# USB2_host_otg.net
KiCad netlist of a schematic drawn in Altium Designer
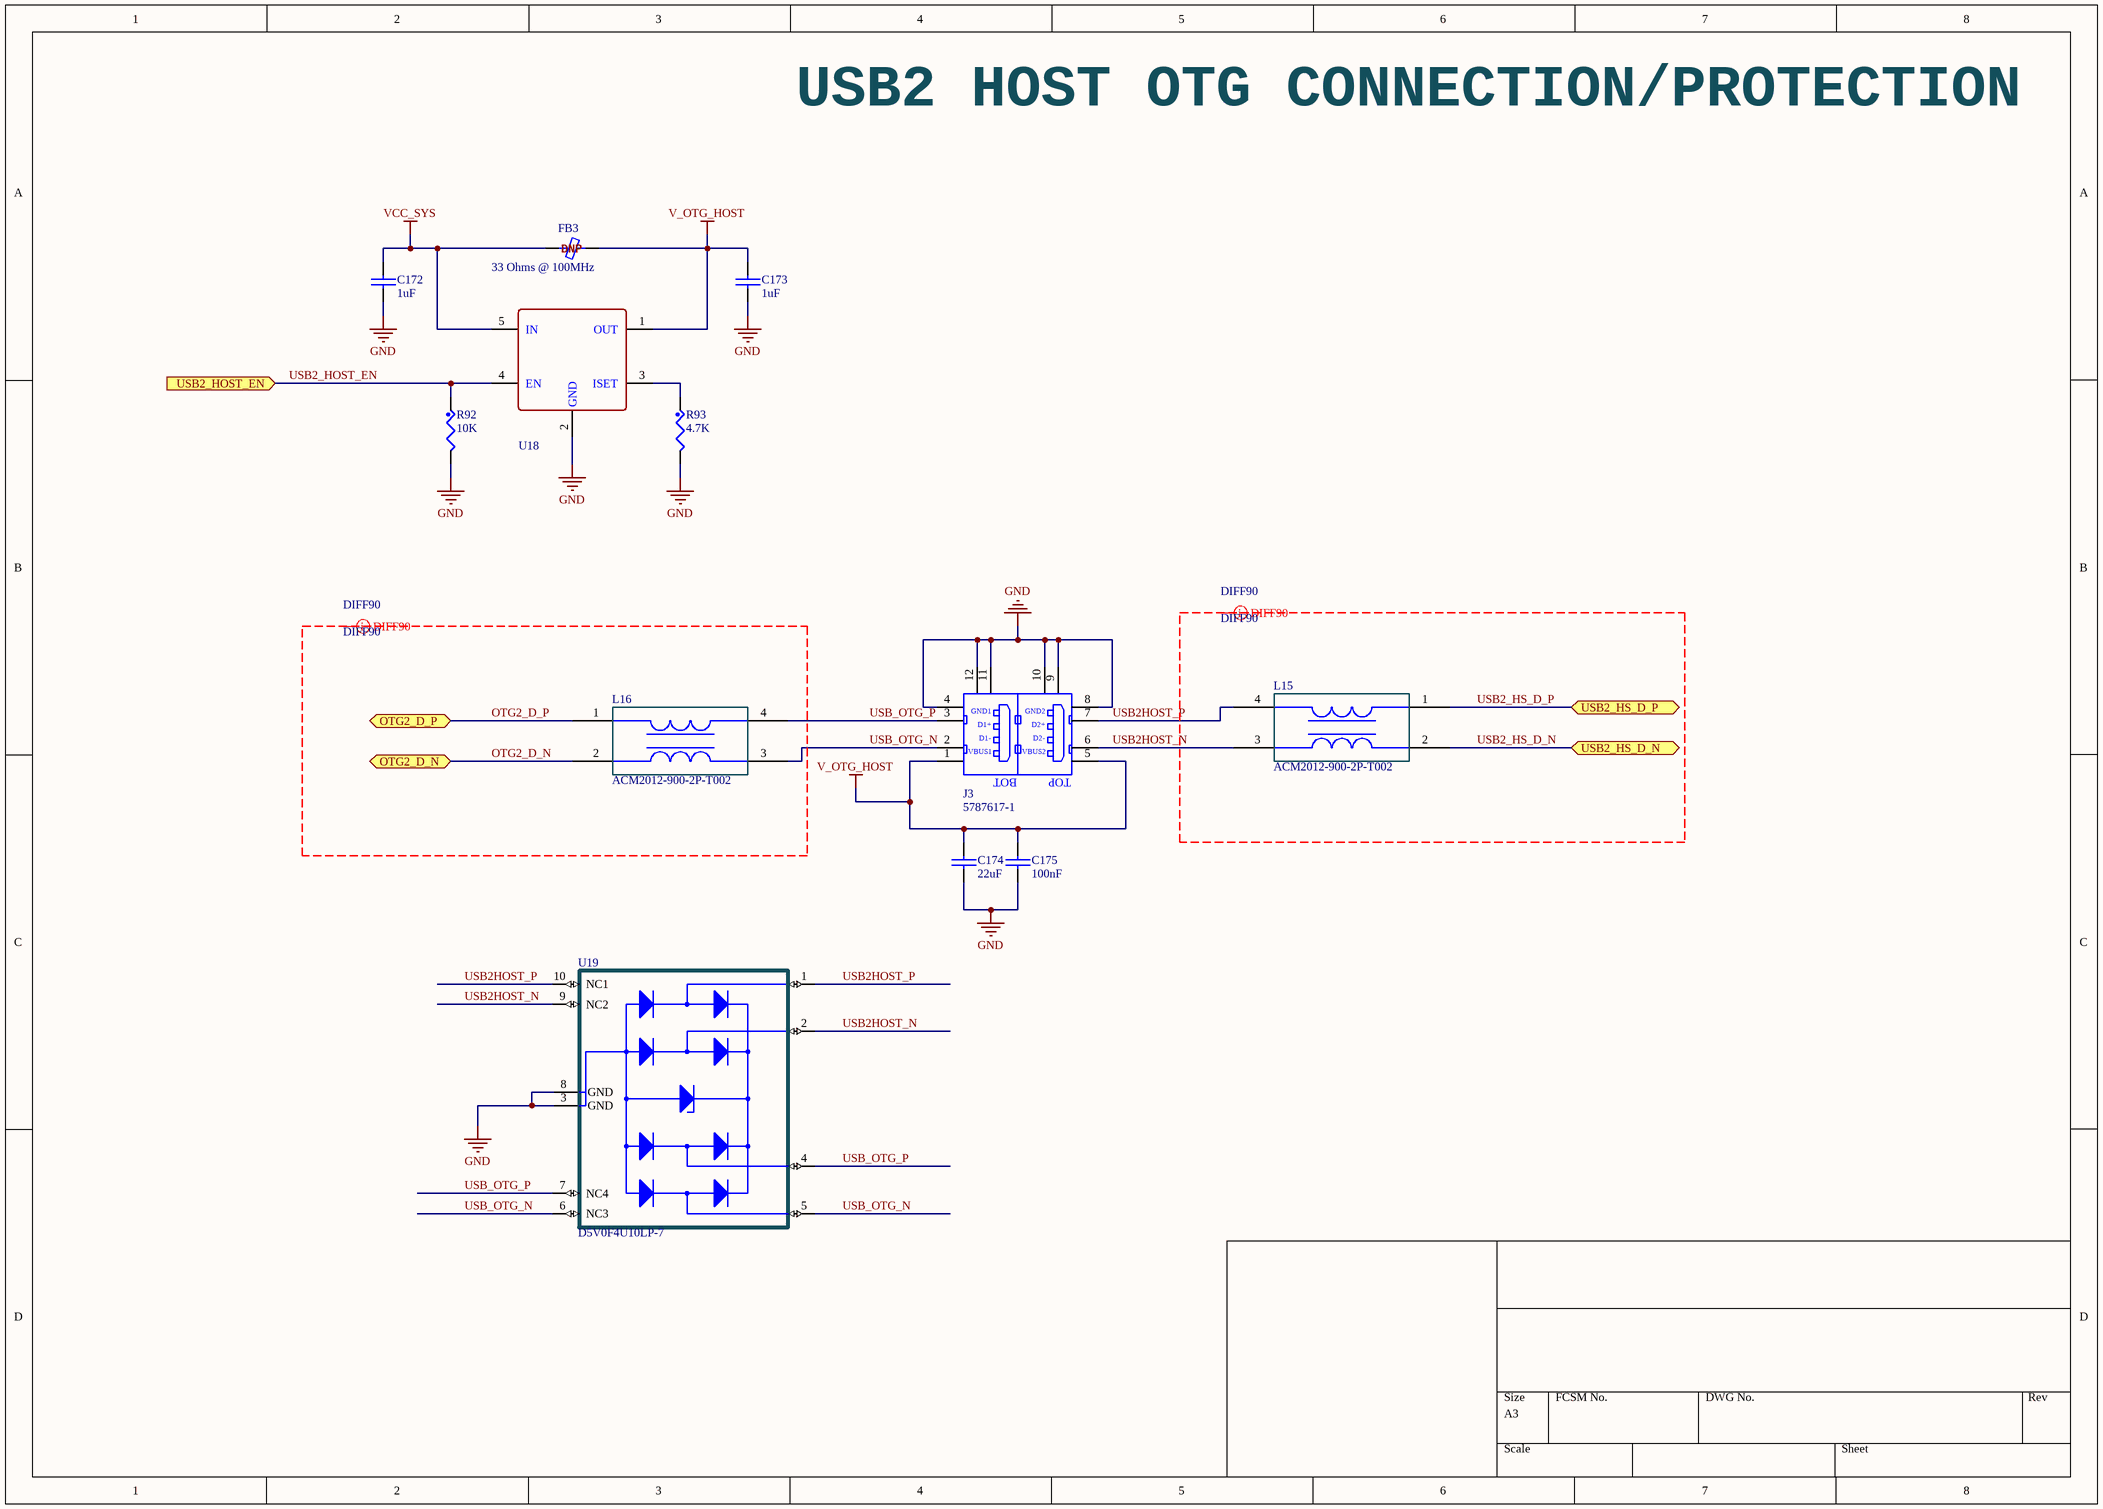
[diagram p0: USB2_host_otg.SchDoc]

(export (version "E")
  (design (tool "Eeschema 10.0.6"))
  (components
    (comp (ref "C172")
      (value "1uF")
      (footprint "0603_CC")
      (libsource (lib "AAR_RockChip_RK3328") (part "CAP_NP"))
    )
    (comp (ref "C173")
      (value "1uF")
      (footprint "0603_CC")
      (libsource (lib "AAR_RockChip_RK3328") (part "CAP_NP"))
    )
    (comp (ref "C174")
      (value "22uF")
      (footprint "0603_CC")
      (libsource (lib "AAR_RockChip_RK3328") (part "CAP_NP"))
    )
    (comp (ref "C175")
      (value "100nF")
      (footprint "0402_CC - C")
      (libsource (lib "AAR_RockChip_RK3328") (part "CAP_NP"))
    )
    (comp (ref "FB3")
      (value "33 Ohms @ 100MHz")
      (footprint "FER 0805_2012")
      (description "FERRITE BEAD 33 OHM 0805 1LN")
      (fields (field (name "PART NUMBER") "Z0805C330ASMST") (field (name "MANUFACTURER") "KEMET"))
      (libsource (lib "Celestial Altium Library - altium_library") (part "Ferrite Chip"))
    )
    (comp (ref "J3")
      (value "5787617-1")
      (footprint "USB-2A")
      (description "CONN RCPT R/A 4OVER4POS GOLD PCB")
      (fields (field (name "MANUFACTURER") "TE Connectivity"))
      (libsource (lib "AAR_RockChip_RK3328") (part "5787617-1_v1.1"))
    )
    (comp (ref "L15")
      (value "ACM2012-900-2P-T002")
      (footprint "FP-ACM2012-MFG")
      (description "CMC 400MA 2LN 90 OHM SMD")
      (fields (field (name "COPYRIGHT") "Copyright (C) 2022 Ultra Librarian. All rights reserved."))
      (libsource (lib "") (part "ACM2012-900-2P-T002_1"))
    )
    (comp (ref "L16")
      (value "ACM2012-900-2P-T002")
      (footprint "FP-ACM2012-MFG")
      (description "CMC 400MA 2LN 90 OHM SMD")
      (fields (field (name "COPYRIGHT") "Copyright (C) 2022 Ultra Librarian. All rights reserved."))
      (libsource (lib "AAR_RockChip_RK3328") (part "ACM2012-900-2P-T002"))
    )
    (comp (ref "R92")
      (value "10K")
      (footprint "0402_CR")
      (libsource (lib "AAR_RockChip_RK3328") (part "RES"))
    )
    (comp (ref "R93")
      (value "4.7K")
      (footprint "0402_CR")
      (libsource (lib "AAR_RockChip_RK3328") (part "RES"))
    )
    (comp (ref "U18")
      (value "Switch")
      (footprint "SOT23_5")
      (fields (field (name "MFR_PART_NO") "SY6280AAC") (field (name "MANUFACTURER") "Silergy"))
      (libsource (lib "AAR_RockChip_RK3328") (part "SY6280A"))
    )
    (comp (ref "U19")
      (value "D5V0F4U10LP-7")
      (footprint "TI_TPD4E05U06DQAR")
      (description "TVS DIODE 5.5VWM 12VC U-DFN2510")
      (fields (field (name "MFR") "Diodes Incorporated") (field (name "CREATOR") "AAR"))
      (libsource (lib "AAR_RockChip_RK3328") (part "D5V0F4U10LP-7"))
    )
  )
  (nets
    (net (code "1") (name "/OTG2_D_N") (class "Default")
      (node (ref "L16") (pin "2") (pinfunction "2_2") (pintype "passive"))
    )
    (net (code "2") (name "/OTG2_D_P") (class "Default")
      (node (ref "L16") (pin "1") (pinfunction "1_1") (pintype "passive"))
    )
    (net (code "3") (name "/USB2HOST_N") (class "Default")
      (node (ref "J3") (pin "6") (pinfunction "D2-_6") (pintype "passive"))
      (node (ref "L15") (pin "3") (pinfunction "3_3") (pintype "passive"))
      (node (ref "U19") (pin "2") (pinfunction "D1-_2") (pintype "bidirectional"))
      (node (ref "U19") (pin "9") (pinfunction "NC2_9") (pintype "bidirectional"))
    )
    (net (code "4") (name "/USB2HOST_P") (class "Default")
      (node (ref "J3") (pin "7") (pinfunction "D2+_7") (pintype "passive"))
      (node (ref "L15") (pin "4") (pinfunction "4_4") (pintype "passive"))
      (node (ref "U19") (pin "1") (pinfunction "D1+_1") (pintype "bidirectional"))
      (node (ref "U19") (pin "10") (pinfunction "NC1_10") (pintype "bidirectional"))
    )
    (net (code "5") (name "/USB2_HOST_EN") (class "Default")
      (node (ref "R92") (pin "1") (pinfunction "1_1") (pintype "passive"))
      (node (ref "U18") (pin "4") (pinfunction "EN_4") (pintype "open_collector"))
    )
    (net (code "6") (name "/USB2_HS_D_N") (class "Default")
      (node (ref "L15") (pin "2") (pinfunction "2_2") (pintype "passive"))
    )
    (net (code "7") (name "/USB2_HS_D_P") (class "Default")
      (node (ref "L15") (pin "1") (pinfunction "1_1") (pintype "passive"))
    )
    (net (code "8") (name "/USB_OTG_N") (class "Default")
      (node (ref "J3") (pin "2") (pinfunction "D-_2") (pintype "passive"))
      (node (ref "L16") (pin "3") (pinfunction "3_3") (pintype "passive"))
      (node (ref "U19") (pin "5") (pinfunction "D2-_5") (pintype "bidirectional"))
      (node (ref "U19") (pin "6") (pinfunction "NC3_6") (pintype "bidirectional"))
    )
    (net (code "9") (name "/USB_OTG_P") (class "Default")
      (node (ref "J3") (pin "3") (pinfunction "D+_3") (pintype "passive"))
      (node (ref "L16") (pin "4") (pinfunction "4_4") (pintype "passive"))
      (node (ref "U19") (pin "4") (pinfunction "D2+_4") (pintype "bidirectional"))
      (node (ref "U19") (pin "7") (pinfunction "NC4_7") (pintype "bidirectional"))
    )
    (net (code "10") (name "GND") (class "Default")
      (node (ref "C172") (pin "2") (pinfunction "2_2") (pintype "passive"))
      (node (ref "C173") (pin "2") (pinfunction "2_2") (pintype "passive"))
      (node (ref "C174") (pin "2") (pinfunction "2_2") (pintype "passive"))
      (node (ref "C175") (pin "2") (pinfunction "2_2") (pintype "passive"))
      (node (ref "J3") (pin "10") (pinfunction "SHIELD_10") (pintype "passive"))
      (node (ref "J3") (pin "11") (pinfunction "SHIELD_11") (pintype "passive"))
      (node (ref "J3") (pin "12") (pinfunction "SHIELD_12") (pintype "passive"))
      (node (ref "J3") (pin "4") (pinfunction "GND_4") (pintype "passive"))
      (node (ref "J3") (pin "8") (pinfunction "GND_8") (pintype "passive"))
      (node (ref "J3") (pin "9") (pinfunction "SHIELD_9") (pintype "passive"))
      (node (ref "R92") (pin "2") (pinfunction "2_2") (pintype "passive"))
      (node (ref "R93") (pin "2") (pinfunction "2_2") (pintype "passive"))
      (node (ref "U18") (pin "2") (pinfunction "GND_2") (pintype "power_in"))
      (node (ref "U19") (pin "3") (pinfunction "GND_3") (pintype "power_in"))
      (node (ref "U19") (pin "8") (pinfunction "GND_8") (pintype "power_in"))
    )
    (net (code "11") (name "Net-(U18-ISET)") (class "Default")
      (node (ref "R93") (pin "1") (pinfunction "1_1") (pintype "passive"))
      (node (ref "U18") (pin "3") (pinfunction "ISET_3") (pintype "power_in"))
    )
    (net (code "12") (name "VCC_SYS") (class "Default")
      (node (ref "C172") (pin "1") (pinfunction "1_1") (pintype "passive"))
      (node (ref "FB3") (pin "1") (pinfunction "1_1") (pintype "passive"))
      (node (ref "U18") (pin "5") (pinfunction "IN_5") (pintype "power_in"))
    )
    (net (code "13") (name "V_OTG_HOST") (class "Default")
      (node (ref "C173") (pin "1") (pinfunction "1_1") (pintype "passive"))
      (node (ref "C174") (pin "1") (pinfunction "1_1") (pintype "passive"))
      (node (ref "C175") (pin "1") (pinfunction "1_1") (pintype "passive"))
      (node (ref "FB3") (pin "2") (pinfunction "2_2") (pintype "passive"))
      (node (ref "J3") (pin "1") (pinfunction "VBUS_1") (pintype "passive"))
      (node (ref "J3") (pin "5") (pinfunction "VBUS2_5") (pintype "passive"))
      (node (ref "U18") (pin "1") (pinfunction "OUT_1") (pintype "power_in"))
    )
  )
)
